# RADIO.net
KiCad netlist of a schematic drawn in EAGLE
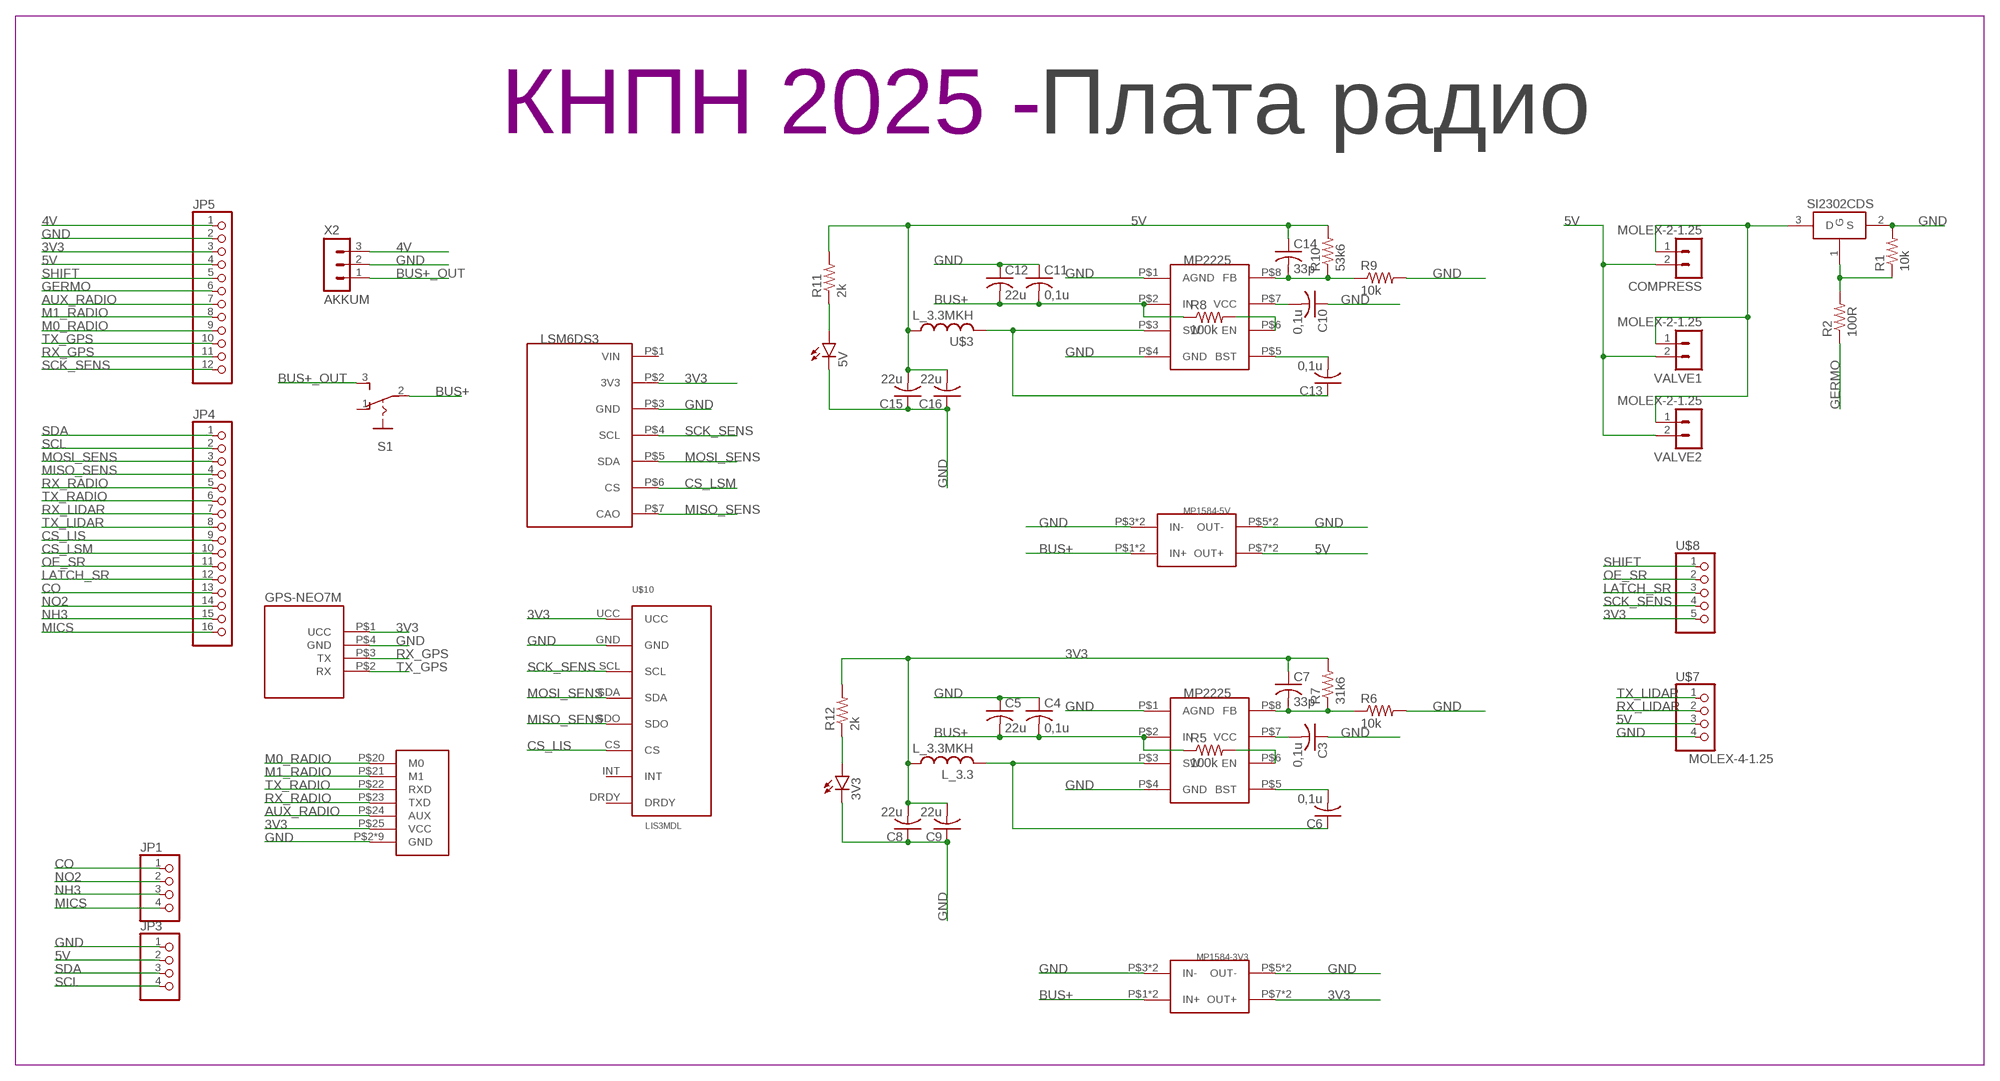
[diagram p0: schematic, sheet 1]

(export (version "E")
  (design (tool "Eeschema 10.0.6"))
  (components
    (comp (ref "3V3")
      (value "LEDCHIP-LED0603")
      (footprint "eagle-import:CHIP-LED0603")
      (libsource (lib "eagle-import") (part "LEDCHIP-LED0603"))
    )
    (comp (ref "5V")
      (value "LEDCHIP-LED0603")
      (footprint "eagle-import:CHIP-LED0603")
      (libsource (lib "eagle-import") (part "LEDCHIP-LED0603"))
    )
    (comp (ref "C3")
      (value "0,1u")
      (footprint "eagle-import:C0603")
      (libsource (lib "eagle-import") (part "C-USC0603"))
    )
    (comp (ref "C4")
      (value "0,1u")
      (footprint "eagle-import:C1206")
      (libsource (lib "eagle-import") (part "C-USC1206"))
    )
    (comp (ref "C5")
      (value "22u")
      (footprint "eagle-import:C0603")
      (libsource (lib "eagle-import") (part "C-USC0603"))
    )
    (comp (ref "C6")
      (value "0,1u")
      (footprint "eagle-import:C0603")
      (libsource (lib "eagle-import") (part "C-USC0603"))
    )
    (comp (ref "C7")
      (value "33p")
      (footprint "eagle-import:C0603")
      (libsource (lib "eagle-import") (part "C-USC0603"))
    )
    (comp (ref "C8")
      (value "22u")
      (footprint "eagle-import:C1206")
      (libsource (lib "eagle-import") (part "C-USC1206"))
    )
    (comp (ref "C9")
      (value "22u")
      (footprint "eagle-import:C1206")
      (libsource (lib "eagle-import") (part "C-USC1206"))
    )
    (comp (ref "C10")
      (value "0,1u")
      (footprint "eagle-import:C0603")
      (libsource (lib "eagle-import") (part "C-USC0603"))
    )
    (comp (ref "C11")
      (value "0,1u")
      (footprint "eagle-import:C1206")
      (libsource (lib "eagle-import") (part "C-USC1206"))
    )
    (comp (ref "C12")
      (value "22u")
      (footprint "eagle-import:C0603")
      (libsource (lib "eagle-import") (part "C-USC0603"))
    )
    (comp (ref "C13")
      (value "0,1u")
      (footprint "eagle-import:C0603")
      (libsource (lib "eagle-import") (part "C-USC0603"))
    )
    (comp (ref "C14")
      (value "33p")
      (footprint "eagle-import:C0603")
      (libsource (lib "eagle-import") (part "C-USC0603"))
    )
    (comp (ref "C15")
      (value "22u")
      (footprint "eagle-import:C1206")
      (libsource (lib "eagle-import") (part "C-USC1206"))
    )
    (comp (ref "C16")
      (value "22u")
      (footprint "eagle-import:C1206")
      (libsource (lib "eagle-import") (part "C-USC1206"))
    )
    (comp (ref "COMPRESS")
      (value "MOLEX-2-1.25")
      (footprint "eagle-import:53047-02")
      (libsource (lib "eagle-import") (part "MOLEX-2-1.25"))
    )
    (comp (ref "GPS-NEO7M")
      (value "GPS-NEO7M")
      (footprint "eagle-import:GPS-NEO7M")
      (libsource (lib "eagle-import") (part "GPS-NEO7M"))
    )
    (comp (ref "JP1")
      (value "PINHD-1X4")
      (footprint "eagle-import:1X04")
      (libsource (lib "eagle-import") (part "PINHD-1X4"))
    )
    (comp (ref "JP3")
      (value "PINHD-1X4")
      (footprint "eagle-import:1X04")
      (libsource (lib "eagle-import") (part "PINHD-1X4"))
    )
    (comp (ref "JP4")
      (value "PINHD-1X16")
      (footprint "eagle-import:1X16")
      (libsource (lib "eagle-import") (part "PINHD-1X16"))
    )
    (comp (ref "JP5")
      (value "PINHD-1X12")
      (footprint "eagle-import:1X12")
      (libsource (lib "eagle-import") (part "PINHD-1X12"))
    )
    (comp (ref "LSM6DS3")
      (value "LSM6DS3")
      (footprint "eagle-import:LSM6DS3_WITHOUT")
      (libsource (lib "eagle-import") (part "LSM6DS3_WITHOUT"))
    )
    (comp (ref "L_3.3")
      (value "L_3.3MKH")
      (footprint "eagle-import:L_SPM5020")
      (libsource (lib "eagle-import") (part "L_3.3MKH_5X5"))
    )
    (comp (ref "MP1584-3V3")
      (value "MP1584-B")
      (footprint "eagle-import:MP1584-B")
      (libsource (lib "eagle-import") (part "MP1584-B"))
    )
    (comp (ref "MP1584-5V")
      (value "MP1584")
      (footprint "eagle-import:MP1584-B")
      (libsource (lib "eagle-import") (part "MP1584-B"))
    )
    (comp (ref "R1")
      (value "10k")
      (footprint "eagle-import:R0603")
      (libsource (lib "eagle-import") (part "R-US_R0603"))
    )
    (comp (ref "R2")
      (value "100R")
      (footprint "eagle-import:R0603")
      (libsource (lib "eagle-import") (part "R-US_R0603"))
    )
    (comp (ref "R5")
      (value "100k")
      (footprint "eagle-import:R0603")
      (libsource (lib "eagle-import") (part "R-US_R0603"))
    )
    (comp (ref "R6")
      (value "10k")
      (footprint "eagle-import:R0603")
      (libsource (lib "eagle-import") (part "R-US_R0603"))
    )
    (comp (ref "R7")
      (value "31k6")
      (footprint "eagle-import:R0603")
      (libsource (lib "eagle-import") (part "R-US_R0603"))
    )
    (comp (ref "R8")
      (value "100k")
      (footprint "eagle-import:R0603")
      (libsource (lib "eagle-import") (part "R-US_R0603"))
    )
    (comp (ref "R9")
      (value "10k")
      (footprint "eagle-import:R0603")
      (libsource (lib "eagle-import") (part "R-US_R0603"))
    )
    (comp (ref "R10")
      (value "53k6")
      (footprint "eagle-import:R0603")
      (libsource (lib "eagle-import") (part "R-US_R0603"))
    )
    (comp (ref "R11")
      (value "2k")
      (footprint "eagle-import:R0603")
      (libsource (lib "eagle-import") (part "R-US_R0603"))
    )
    (comp (ref "R12")
      (value "2k")
      (footprint "eagle-import:R0603")
      (libsource (lib "eagle-import") (part "R-US_R0603"))
    )
    (comp (ref "RADIO")
      (value "E220-400T22S")
      (footprint "eagle-import:E220-400T22S")
      (libsource (lib "eagle-import") (part "E220-400T22S"))
    )
    (comp (ref "S1")
      (value "UNICS-SWITCHSS_12D11")
      (footprint "eagle-import:SS_12D11")
      (libsource (lib "eagle-import") (part "UNICS-SWITCHSS_12D11"))
    )
    (comp (ref "SI2302CDS")
      (value "SI2302CDS")
      (footprint "eagle-import:SOT23-3")
      (libsource (lib "eagle-import") (part "SI2302CDS"))
    )
    (comp (ref "U$1")
      (value "Плата радио")
      (footprint "eagle-import:LOGO")
      (libsource (lib "eagle-import") (part "LOGOPCB-{dblquote}{dblquote}"))
    )
    (comp (ref "U$2")
      (value "MP2225")
      (footprint "eagle-import:TSOT23-8")
      (libsource (lib "eagle-import") (part "MP2225"))
    )
    (comp (ref "U$3")
      (value "L_3.3MKH")
      (footprint "eagle-import:L_SPM5020")
      (libsource (lib "eagle-import") (part "L_3.3MKH_5X5"))
    )
    (comp (ref "U$5")
      (value "MP2225")
      (footprint "eagle-import:TSOT23-8")
      (libsource (lib "eagle-import") (part "MP2225"))
    )
    (comp (ref "U$7")
      (value "MOLEX-4-1.25")
      (footprint "eagle-import:53047-04")
      (libsource (lib "eagle-import") (part "MOLEX-4-1.25"))
    )
    (comp (ref "U$8")
      (value "MOLEX-5-1.25")
      (footprint "eagle-import:53047-05")
      (libsource (lib "eagle-import") (part "MOLEX-5-1.25"))
    )
    (comp (ref "U$10")
      (value "LIS3MDL")
      (footprint "eagle-import:LIS3MDL")
      (libsource (lib "eagle-import") (part "LIS3MDL"))
    )
    (comp (ref "VALVE1")
      (value "MOLEX-2-1.25")
      (footprint "eagle-import:53047-02")
      (libsource (lib "eagle-import") (part "MOLEX-2-1.25"))
    )
    (comp (ref "VALVE2")
      (value "MOLEX-2-1.25")
      (footprint "eagle-import:53047-02")
      (libsource (lib "eagle-import") (part "MOLEX-2-1.25"))
    )
    (comp (ref "X2")
      (value "AKKUM")
      (footprint "eagle-import:JST-3-2.5")
      (libsource (lib "eagle-import") (part "JST-3-2.5"))
    )
  )
  (nets
    (net (code "1") (name "/3V3") (class "Default")
      (node (ref "C7") (pin "1") (pinfunction "1_1") (pintype "passive"))
      (node (ref "C8") (pin "2") (pinfunction "2_2") (pintype "passive"))
      (node (ref "C9") (pin "2") (pinfunction "2_2") (pintype "passive"))
      (node (ref "GPS-NEO7M") (pin "P$1") (pinfunction "UCC_P$1") (pintype "bidirectional"))
      (node (ref "JP5") (pin "3") (pinfunction "3_3") (pintype "passive"))
      (node (ref "LSM6DS3") (pin "P$2") (pinfunction "3V3_P$2") (pintype "bidirectional"))
      (node (ref "L_3.3") (pin "P$1") (pinfunction "1_P$1") (pintype "passive"))
      (node (ref "MP1584-3V3") (pin "P$7") (pinfunction "OUT+_P$7") (pintype "bidirectional"))
      (node (ref "MP1584-3V3") (pin "P$8") (pinfunction "OUT+_P$8") (pintype "bidirectional"))
      (node (ref "R12") (pin "2") (pinfunction "2_2") (pintype "passive"))
      (node (ref "R7") (pin "2") (pinfunction "2_2") (pintype "passive"))
      (node (ref "RADIO") (pin "P$25") (pinfunction "VCC_P$25") (pintype "bidirectional"))
      (node (ref "U$10") (pin "UCC") (pinfunction "UCC_UCC") (pintype "bidirectional"))
      (node (ref "U$8") (pin "5") (pinfunction "5_5") (pintype "passive"))
    )
    (net (code "2") (name "/4V") (class "Default")
      (node (ref "JP5") (pin "1") (pinfunction "1_1") (pintype "passive"))
      (node (ref "X2") (pin "3") (pinfunction "3_3") (pintype "passive"))
    )
    (net (code "3") (name "/5V") (class "Default")
      (node (ref "C14") (pin "1") (pinfunction "1_1") (pintype "passive"))
      (node (ref "C15") (pin "2") (pinfunction "2_2") (pintype "passive"))
      (node (ref "C16") (pin "2") (pinfunction "2_2") (pintype "passive"))
      (node (ref "COMPRESS") (pin "2") (pinfunction "2_2") (pintype "passive"))
      (node (ref "JP3") (pin "2") (pinfunction "2_2") (pintype "passive"))
      (node (ref "JP5") (pin "4") (pinfunction "4_4") (pintype "passive"))
      (node (ref "MP1584-5V") (pin "P$7") (pinfunction "OUT+_P$7") (pintype "bidirectional"))
      (node (ref "MP1584-5V") (pin "P$8") (pinfunction "OUT+_P$8") (pintype "bidirectional"))
      (node (ref "R10") (pin "2") (pinfunction "2_2") (pintype "passive"))
      (node (ref "R11") (pin "2") (pinfunction "2_2") (pintype "passive"))
      (node (ref "U$3") (pin "P$1") (pinfunction "1_P$1") (pintype "passive"))
      (node (ref "U$7") (pin "3") (pinfunction "3_3") (pintype "passive"))
      (node (ref "VALVE1") (pin "2") (pinfunction "2_2") (pintype "passive"))
      (node (ref "VALVE2") (pin "2") (pinfunction "2_2") (pintype "passive"))
    )
    (net (code "4") (name "/AUX_RADIO") (class "Default")
      (node (ref "JP5") (pin "7") (pinfunction "7_7") (pintype "passive"))
      (node (ref "RADIO") (pin "P$24") (pinfunction "AUX_P$24") (pintype "bidirectional"))
    )
    (net (code "5") (name "/BUS+") (class "Default")
      (node (ref "C11") (pin "2") (pinfunction "2_2") (pintype "passive"))
      (node (ref "C12") (pin "2") (pinfunction "2_2") (pintype "passive"))
      (node (ref "C4") (pin "2") (pinfunction "2_2") (pintype "passive"))
      (node (ref "C5") (pin "2") (pinfunction "2_2") (pintype "passive"))
      (node (ref "MP1584-3V3") (pin "P$1") (pinfunction "IN+_P$1") (pintype "bidirectional"))
      (node (ref "MP1584-3V3") (pin "P$2") (pinfunction "IN+_P$2") (pintype "bidirectional"))
      (node (ref "MP1584-5V") (pin "P$1") (pinfunction "IN+_P$1") (pintype "bidirectional"))
      (node (ref "MP1584-5V") (pin "P$2") (pinfunction "IN+_P$2") (pintype "bidirectional"))
      (node (ref "R5") (pin "1") (pinfunction "1_1") (pintype "passive"))
      (node (ref "R8") (pin "1") (pinfunction "1_1") (pintype "passive"))
      (node (ref "S1") (pin "2") (pinfunction "P_2") (pintype "passive"))
      (node (ref "U$2") (pin "P$2") (pinfunction "IN_P$2") (pintype "bidirectional"))
      (node (ref "U$5") (pin "P$2") (pinfunction "IN_P$2") (pintype "bidirectional"))
    )
    (net (code "6") (name "/BUS+_OUT") (class "Default")
      (node (ref "S1") (pin "3") (pinfunction "S_3") (pintype "passive"))
      (node (ref "X2") (pin "1") (pinfunction "1_1") (pintype "passive"))
    )
    (net (code "7") (name "/CO") (class "Default")
      (node (ref "JP1") (pin "1") (pinfunction "1_1") (pintype "passive"))
      (node (ref "JP4") (pin "13") (pinfunction "13_13") (pintype "passive"))
    )
    (net (code "8") (name "/CS_LIS") (class "Default")
      (node (ref "JP4") (pin "9") (pinfunction "9_9") (pintype "passive"))
      (node (ref "U$10") (pin "CS") (pinfunction "CS_CS") (pintype "bidirectional"))
    )
    (net (code "9") (name "/CS_LSM") (class "Default")
      (node (ref "JP4") (pin "10") (pinfunction "10_10") (pintype "passive"))
      (node (ref "LSM6DS3") (pin "P$6") (pinfunction "CS_P$6") (pintype "bidirectional"))
    )
    (net (code "10") (name "/GERMO") (class "Default")
      (node (ref "JP5") (pin "6") (pinfunction "6_6") (pintype "passive"))
      (node (ref "R2") (pin "1") (pinfunction "1_1") (pintype "passive"))
    )
    (net (code "11") (name "/GND") (class "Default")
      (node (ref "3V3") (pin "C") (pinfunction "C_C") (pintype "passive"))
      (node (ref "5V") (pin "C") (pinfunction "C_C") (pintype "passive"))
      (node (ref "C10") (pin "1") (pinfunction "1_1") (pintype "passive"))
      (node (ref "C11") (pin "1") (pinfunction "1_1") (pintype "passive"))
      (node (ref "C12") (pin "1") (pinfunction "1_1") (pintype "passive"))
      (node (ref "C15") (pin "1") (pinfunction "1_1") (pintype "passive"))
      (node (ref "C16") (pin "1") (pinfunction "1_1") (pintype "passive"))
      (node (ref "C3") (pin "1") (pinfunction "1_1") (pintype "passive"))
      (node (ref "C4") (pin "1") (pinfunction "1_1") (pintype "passive"))
      (node (ref "C5") (pin "1") (pinfunction "1_1") (pintype "passive"))
      (node (ref "C8") (pin "1") (pinfunction "1_1") (pintype "passive"))
      (node (ref "C9") (pin "1") (pinfunction "1_1") (pintype "passive"))
      (node (ref "GPS-NEO7M") (pin "P$4") (pinfunction "GND_P$4") (pintype "bidirectional"))
      (node (ref "JP3") (pin "1") (pinfunction "1_1") (pintype "passive"))
      (node (ref "JP5") (pin "2") (pinfunction "2_2") (pintype "passive"))
      (node (ref "LSM6DS3") (pin "P$3") (pinfunction "GND_P$3") (pintype "bidirectional"))
      (node (ref "MP1584-3V3") (pin "P$3") (pinfunction "IN-_P$3") (pintype "bidirectional"))
      (node (ref "MP1584-3V3") (pin "P$4") (pinfunction "IN-_P$4") (pintype "bidirectional"))
      (node (ref "MP1584-3V3") (pin "P$5") (pinfunction "OUT-_P$5") (pintype "bidirectional"))
      (node (ref "MP1584-3V3") (pin "P$6") (pinfunction "OUT-_P$6") (pintype "bidirectional"))
      (node (ref "MP1584-5V") (pin "P$3") (pinfunction "IN-_P$3") (pintype "bidirectional"))
      (node (ref "MP1584-5V") (pin "P$4") (pinfunction "IN-_P$4") (pintype "bidirectional"))
      (node (ref "MP1584-5V") (pin "P$5") (pinfunction "OUT-_P$5") (pintype "bidirectional"))
      (node (ref "MP1584-5V") (pin "P$6") (pinfunction "OUT-_P$6") (pintype "bidirectional"))
      (node (ref "R1") (pin "2") (pinfunction "2_2") (pintype "passive"))
      (node (ref "R6") (pin "2") (pinfunction "2_2") (pintype "passive"))
      (node (ref "R9") (pin "2") (pinfunction "2_2") (pintype "passive"))
      (node (ref "RADIO") (pin "P$11") (pinfunction "GND_P$11") (pintype "bidirectional"))
      (node (ref "RADIO") (pin "P$13") (pinfunction "GND_P$13") (pintype "bidirectional"))
      (node (ref "RADIO") (pin "P$14") (pinfunction "GND_P$14") (pintype "bidirectional"))
      (node (ref "RADIO") (pin "P$15") (pinfunction "GND_P$15") (pintype "bidirectional"))
      (node (ref "RADIO") (pin "P$16") (pinfunction "GND_P$16") (pintype "bidirectional"))
      (node (ref "RADIO") (pin "P$19") (pinfunction "GND_P$19") (pintype "bidirectional"))
      (node (ref "RADIO") (pin "P$2") (pinfunction "GND_P$2") (pintype "bidirectional"))
      (node (ref "RADIO") (pin "P$26") (pinfunction "GND_P$26") (pintype "bidirectional"))
      (node (ref "RADIO") (pin "P$8") (pinfunction "GND_P$8") (pintype "bidirectional"))
      (node (ref "SI2302CDS") (pin "2") (pinfunction "S_2") (pintype "bidirectional"))
      (node (ref "U$10") (pin "GND") (pinfunction "GND_GND") (pintype "bidirectional"))
      (node (ref "U$2") (pin "P$1") (pinfunction "AGND_P$1") (pintype "bidirectional"))
      (node (ref "U$2") (pin "P$4") (pinfunction "GND_P$4") (pintype "bidirectional"))
      (node (ref "U$5") (pin "P$1") (pinfunction "AGND_P$1") (pintype "bidirectional"))
      (node (ref "U$5") (pin "P$4") (pinfunction "GND_P$4") (pintype "bidirectional"))
      (node (ref "U$7") (pin "4") (pinfunction "4_4") (pintype "passive"))
      (node (ref "X2") (pin "2") (pinfunction "2_2") (pintype "passive"))
    )
    (net (code "12") (name "/LATCH_SR") (class "Default")
      (node (ref "JP4") (pin "12") (pinfunction "12_12") (pintype "passive"))
      (node (ref "U$8") (pin "3") (pinfunction "3_3") (pintype "passive"))
    )
    (net (code "13") (name "/M0_RADIO") (class "Default")
      (node (ref "JP5") (pin "9") (pinfunction "9_9") (pintype "passive"))
      (node (ref "RADIO") (pin "P$20") (pinfunction "M0_P$20") (pintype "bidirectional"))
    )
    (net (code "14") (name "/M1_RADIO") (class "Default")
      (node (ref "JP5") (pin "8") (pinfunction "8_8") (pintype "passive"))
      (node (ref "RADIO") (pin "P$21") (pinfunction "M1_P$21") (pintype "bidirectional"))
    )
    (net (code "15") (name "/MICS") (class "Default")
      (node (ref "JP1") (pin "4") (pinfunction "4_4") (pintype "passive"))
      (node (ref "JP4") (pin "16") (pinfunction "16_16") (pintype "passive"))
    )
    (net (code "16") (name "/MISO_SENS") (class "Default")
      (node (ref "JP4") (pin "4") (pinfunction "4_4") (pintype "passive"))
      (node (ref "LSM6DS3") (pin "P$7") (pinfunction "CAO_P$7") (pintype "bidirectional"))
      (node (ref "U$10") (pin "SDO") (pinfunction "SDO_SDO") (pintype "bidirectional"))
    )
    (net (code "17") (name "/MOSI_SENS") (class "Default")
      (node (ref "JP4") (pin "3") (pinfunction "3_3") (pintype "passive"))
      (node (ref "LSM6DS3") (pin "P$5") (pinfunction "SDA_P$5") (pintype "bidirectional"))
      (node (ref "U$10") (pin "SDA") (pinfunction "SDA_SDA") (pintype "bidirectional"))
    )
    (net (code "18") (name "/NH3") (class "Default")
      (node (ref "JP1") (pin "3") (pinfunction "3_3") (pintype "passive"))
      (node (ref "JP4") (pin "15") (pinfunction "15_15") (pintype "passive"))
    )
    (net (code "19") (name "/NO2") (class "Default")
      (node (ref "JP1") (pin "2") (pinfunction "2_2") (pintype "passive"))
      (node (ref "JP4") (pin "14") (pinfunction "14_14") (pintype "passive"))
    )
    (net (code "20") (name "/OE_SR") (class "Default")
      (node (ref "JP4") (pin "11") (pinfunction "11_11") (pintype "passive"))
      (node (ref "U$8") (pin "2") (pinfunction "2_2") (pintype "passive"))
    )
    (net (code "21") (name "/RX_GPS") (class "Default")
      (node (ref "GPS-NEO7M") (pin "P$3") (pinfunction "TX_P$3") (pintype "bidirectional"))
      (node (ref "JP5") (pin "11") (pinfunction "11_11") (pintype "passive"))
    )
    (net (code "22") (name "/RX_LIDAR") (class "Default")
      (node (ref "JP4") (pin "7") (pinfunction "7_7") (pintype "passive"))
      (node (ref "U$7") (pin "2") (pinfunction "2_2") (pintype "passive"))
    )
    (net (code "23") (name "/RX_RADIO") (class "Default")
      (node (ref "JP4") (pin "5") (pinfunction "5_5") (pintype "passive"))
      (node (ref "RADIO") (pin "P$23") (pinfunction "TXD_P$23") (pintype "bidirectional"))
    )
    (net (code "24") (name "/SCK_SENS") (class "Default")
      (node (ref "JP5") (pin "12") (pinfunction "12_12") (pintype "passive"))
      (node (ref "LSM6DS3") (pin "P$4") (pinfunction "SCL_P$4") (pintype "bidirectional"))
      (node (ref "U$10") (pin "SCL") (pinfunction "SCL_SCL") (pintype "bidirectional"))
      (node (ref "U$8") (pin "4") (pinfunction "4_4") (pintype "passive"))
    )
    (net (code "25") (name "/SCL") (class "Default")
      (node (ref "JP3") (pin "4") (pinfunction "4_4") (pintype "passive"))
      (node (ref "JP4") (pin "2") (pinfunction "2_2") (pintype "passive"))
    )
    (net (code "26") (name "/SDA") (class "Default")
      (node (ref "JP3") (pin "3") (pinfunction "3_3") (pintype "passive"))
      (node (ref "JP4") (pin "1") (pinfunction "1_1") (pintype "passive"))
    )
    (net (code "27") (name "/SHIFT") (class "Default")
      (node (ref "JP5") (pin "5") (pinfunction "5_5") (pintype "passive"))
      (node (ref "U$8") (pin "1") (pinfunction "1_1") (pintype "passive"))
    )
    (net (code "28") (name "/TX_GPS") (class "Default")
      (node (ref "GPS-NEO7M") (pin "P$2") (pinfunction "RX_P$2") (pintype "bidirectional"))
      (node (ref "JP5") (pin "10") (pinfunction "10_10") (pintype "passive"))
    )
    (net (code "29") (name "/TX_LIDAR") (class "Default")
      (node (ref "JP4") (pin "8") (pinfunction "8_8") (pintype "passive"))
      (node (ref "U$7") (pin "1") (pinfunction "1_1") (pintype "passive"))
    )
    (net (code "30") (name "/TX_RADIO") (class "Default")
      (node (ref "JP4") (pin "6") (pinfunction "6_6") (pintype "passive"))
      (node (ref "RADIO") (pin "P$22") (pinfunction "RXD_P$22") (pintype "bidirectional"))
    )
    (net (code "31") (name "Net-(3V3-PadA)") (class "Default")
      (node (ref "3V3") (pin "A") (pinfunction "A_A") (pintype "passive"))
      (node (ref "R12") (pin "1") (pinfunction "1_1") (pintype "passive"))
    )
    (net (code "32") (name "Net-(5V-PadA)") (class "Default")
      (node (ref "5V") (pin "A") (pinfunction "A_A") (pintype "passive"))
      (node (ref "R11") (pin "1") (pinfunction "1_1") (pintype "passive"))
    )
    (net (code "33") (name "Net-(L_3.3-2)") (class "Default")
      (node (ref "C6") (pin "1") (pinfunction "1_1") (pintype "passive"))
      (node (ref "L_3.3") (pin "P$2") (pinfunction "2_P$2") (pintype "passive"))
      (node (ref "U$2") (pin "P$3") (pinfunction "SW_P$3") (pintype "bidirectional"))
    )
    (net (code "34") (name "Net-(SI2302CDS-D)") (class "Default")
      (node (ref "COMPRESS") (pin "1") (pinfunction "1_1") (pintype "passive"))
      (node (ref "SI2302CDS") (pin "3") (pinfunction "D_3") (pintype "bidirectional"))
      (node (ref "VALVE1") (pin "1") (pinfunction "1_1") (pintype "passive"))
      (node (ref "VALVE2") (pin "1") (pinfunction "1_1") (pintype "passive"))
    )
    (net (code "35") (name "Net-(SI2302CDS-G)") (class "Default")
      (node (ref "R1") (pin "1") (pinfunction "1_1") (pintype "passive"))
      (node (ref "R2") (pin "2") (pinfunction "2_2") (pintype "passive"))
      (node (ref "SI2302CDS") (pin "1") (pinfunction "G_1") (pintype "bidirectional"))
    )
    (net (code "36") (name "Net-(U$2-BST)") (class "Default")
      (node (ref "C6") (pin "2") (pinfunction "2_2") (pintype "passive"))
      (node (ref "U$2") (pin "P$5") (pinfunction "BST_P$5") (pintype "bidirectional"))
    )
    (net (code "37") (name "Net-(U$2-EN)") (class "Default")
      (node (ref "R5") (pin "2") (pinfunction "2_2") (pintype "passive"))
      (node (ref "U$2") (pin "P$6") (pinfunction "EN_P$6") (pintype "bidirectional"))
    )
    (net (code "38") (name "Net-(U$2-FB)") (class "Default")
      (node (ref "C7") (pin "2") (pinfunction "2_2") (pintype "passive"))
      (node (ref "R6") (pin "1") (pinfunction "1_1") (pintype "passive"))
      (node (ref "R7") (pin "1") (pinfunction "1_1") (pintype "passive"))
      (node (ref "U$2") (pin "P$8") (pinfunction "FB_P$8") (pintype "bidirectional"))
    )
    (net (code "39") (name "Net-(U$2-VCC)") (class "Default")
      (node (ref "C3") (pin "2") (pinfunction "2_2") (pintype "passive"))
      (node (ref "U$2") (pin "P$7") (pinfunction "VCC_P$7") (pintype "bidirectional"))
    )
    (net (code "40") (name "Net-(U$3-2)") (class "Default")
      (node (ref "C13") (pin "1") (pinfunction "1_1") (pintype "passive"))
      (node (ref "U$3") (pin "P$2") (pinfunction "2_P$2") (pintype "passive"))
      (node (ref "U$5") (pin "P$3") (pinfunction "SW_P$3") (pintype "bidirectional"))
    )
    (net (code "41") (name "Net-(U$5-BST)") (class "Default")
      (node (ref "C13") (pin "2") (pinfunction "2_2") (pintype "passive"))
      (node (ref "U$5") (pin "P$5") (pinfunction "BST_P$5") (pintype "bidirectional"))
    )
    (net (code "42") (name "Net-(U$5-EN)") (class "Default")
      (node (ref "R8") (pin "2") (pinfunction "2_2") (pintype "passive"))
      (node (ref "U$5") (pin "P$6") (pinfunction "EN_P$6") (pintype "bidirectional"))
    )
    (net (code "43") (name "Net-(U$5-FB)") (class "Default")
      (node (ref "C14") (pin "2") (pinfunction "2_2") (pintype "passive"))
      (node (ref "R10") (pin "1") (pinfunction "1_1") (pintype "passive"))
      (node (ref "R9") (pin "1") (pinfunction "1_1") (pintype "passive"))
      (node (ref "U$5") (pin "P$8") (pinfunction "FB_P$8") (pintype "bidirectional"))
    )
    (net (code "44") (name "Net-(U$5-VCC)") (class "Default")
      (node (ref "C10") (pin "2") (pinfunction "2_2") (pintype "passive"))
      (node (ref "U$5") (pin "P$7") (pinfunction "VCC_P$7") (pintype "bidirectional"))
    )
    (net (code "45") (name "unconnected-(LSM6DS3-VIN-PadP$1)") (class "Default")
      (node (ref "LSM6DS3") (pin "P$1") (pinfunction "VIN_P$1") (pintype "bidirectional"))
    )
    (net (code "46") (name "unconnected-(S1-O-Pad1)") (class "Default")
      (node (ref "S1") (pin "1") (pinfunction "O_1") (pintype "passive"))
    )
    (net (code "47") (name "unconnected-(U$10-PadDRDY)") (class "Default")
      (node (ref "U$10") (pin "DRDY") (pinfunction "DRDY_DRDY") (pintype "bidirectional"))
    )
    (net (code "48") (name "unconnected-(U$10-PadINT)") (class "Default")
      (node (ref "U$10") (pin "INT") (pinfunction "INT_INT") (pintype "bidirectional"))
    )
  )
)
